# 12.net
KiCad netlist of a schematic drawn in EAGLE
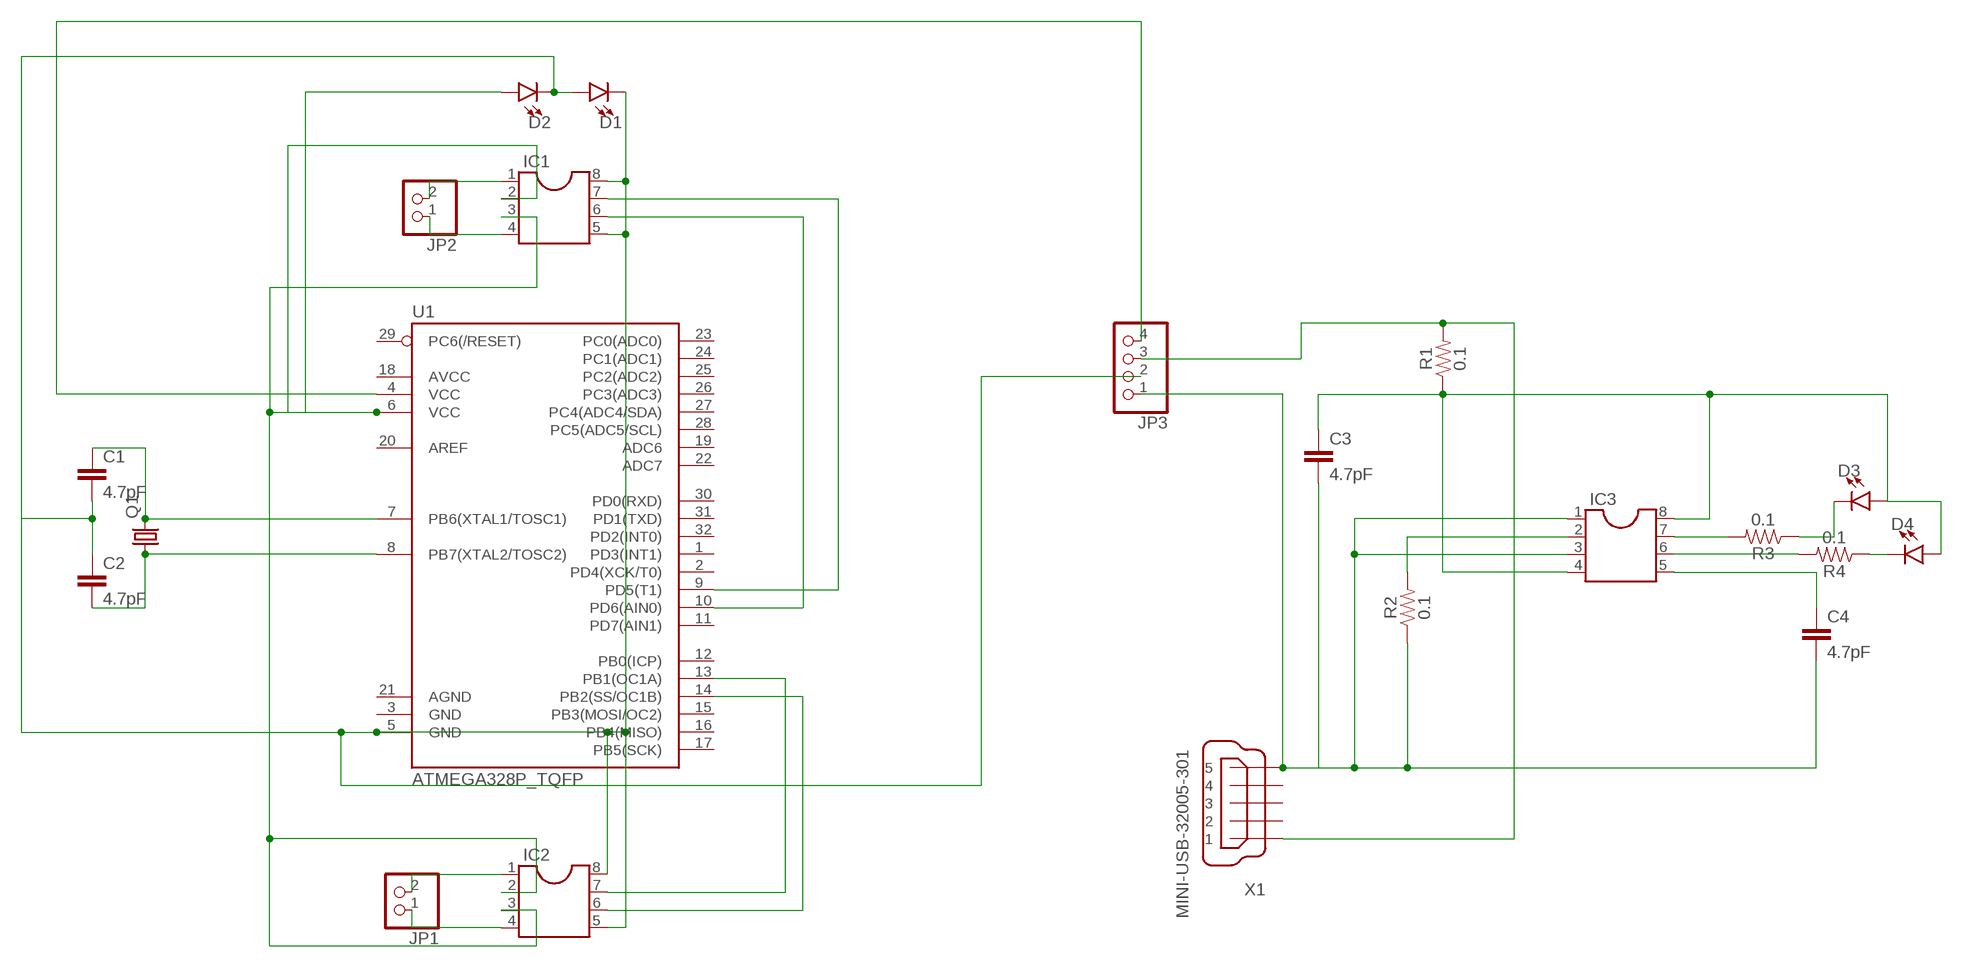
[diagram p0: schematic, sheet 1]

(export (version "E")
  (design (tool "Eeschema 10.0.6"))
  (components
    (comp (ref "C1")
      (value "4.7pF")
      (footprint "eagle-import:0603")
      (libsource (lib "eagle-import") (part "4.7PF-0603-50V-5%"))
    )
    (comp (ref "C2")
      (value "4.7pF")
      (footprint "eagle-import:0603")
      (libsource (lib "eagle-import") (part "4.7PF-0603-50V-5%"))
    )
    (comp (ref "C3")
      (value "4.7pF")
      (footprint "eagle-import:0603")
      (libsource (lib "eagle-import") (part "4.7PF-0603-50V-5%"))
    )
    (comp (ref "C4")
      (value "4.7pF")
      (footprint "eagle-import:0603")
      (libsource (lib "eagle-import") (part "4.7PF-0603-50V-5%"))
    )
    (comp (ref "D1")
      (value "LED0603")
      (footprint "eagle-import:LED-0603")
      (libsource (lib "eagle-import") (part "LED0603"))
    )
    (comp (ref "D2")
      (value "LED0603")
      (footprint "eagle-import:LED-0603")
      (libsource (lib "eagle-import") (part "LED0603"))
    )
    (comp (ref "D3")
      (value "LED0603")
      (footprint "eagle-import:LED-0603")
      (libsource (lib "eagle-import") (part "LED0603"))
    )
    (comp (ref "D4")
      (value "LED0603")
      (footprint "eagle-import:LED-0603")
      (libsource (lib "eagle-import") (part "LED0603"))
    )
    (comp (ref "IC1")
      (value "DIL8")
      (footprint "eagle-import:DIL08")
      (libsource (lib "eagle-import") (part "DIL8"))
    )
    (comp (ref "IC2")
      (value "DIL8")
      (footprint "eagle-import:DIL08")
      (libsource (lib "eagle-import") (part "DIL8"))
    )
    (comp (ref "IC3")
      (value "DIL8")
      (footprint "eagle-import:DIL08")
      (libsource (lib "eagle-import") (part "DIL8"))
    )
    (comp (ref "JP1")
      (value "PINHD-1X2")
      (footprint "eagle-import:1X02")
      (libsource (lib "eagle-import") (part "PINHD-1X2"))
    )
    (comp (ref "JP2")
      (value "PINHD-1X2")
      (footprint "eagle-import:1X02")
      (libsource (lib "eagle-import") (part "PINHD-1X2"))
    )
    (comp (ref "JP3")
      (value "PINHD-1X4")
      (footprint "eagle-import:1X04")
      (libsource (lib "eagle-import") (part "PINHD-1X4"))
    )
    (comp (ref "Q1")
      (value "CRYSTALHC49UP")
      (footprint "eagle-import:HC49UP")
      (libsource (lib "eagle-import") (part "CRYSTALHC49UP"))
    )
    (comp (ref "R1")
      (value "0.1")
      (footprint "eagle-import:1210")
      (libsource (lib "eagle-import") (part "0.1OHM-1210-1/2W-1%"))
    )
    (comp (ref "R2")
      (value "0.1")
      (footprint "eagle-import:1210")
      (libsource (lib "eagle-import") (part "0.1OHM-1210-1/2W-1%"))
    )
    (comp (ref "R3")
      (value "0.1")
      (footprint "eagle-import:1210")
      (libsource (lib "eagle-import") (part "0.1OHM-1210-1/2W-1%"))
    )
    (comp (ref "R4")
      (value "0.1")
      (footprint "eagle-import:1210")
      (libsource (lib "eagle-import") (part "0.1OHM-1210-1/2W-1%"))
    )
    (comp (ref "U1")
      (value "ATMEGA328P_TQFP")
      (footprint "eagle-import:TQFP32-08")
      (libsource (lib "eagle-import") (part "ATMEGA328P_TQFP"))
    )
    (comp (ref "X1")
      (value "MINI-USB-32005-301")
      (footprint "eagle-import:32005-301")
      (libsource (lib "eagle-import") (part "MINI-USB-32005-301"))
    )
  )
  (nets
    (net (code "1") (name "Net-(C1-Pad2)") (class "Default")
      (node (ref "C1") (pin "2") (pinfunction "2_2") (pintype "passive"))
      (node (ref "C2") (pin "1") (pinfunction "1_1") (pintype "passive"))
      (node (ref "D1") (pin "A") (pinfunction "A_A") (pintype "passive"))
      (node (ref "D1") (pin "C") (pinfunction "C_C") (pintype "passive"))
      (node (ref "D2") (pin "C") (pinfunction "C_C") (pintype "passive"))
      (node (ref "IC1") (pin "5") (pinfunction "5_5") (pintype "passive"))
      (node (ref "IC1") (pin "8") (pinfunction "8_8") (pintype "passive"))
      (node (ref "IC2") (pin "5") (pinfunction "5_5") (pintype "passive"))
      (node (ref "IC2") (pin "8") (pinfunction "8_8") (pintype "passive"))
      (node (ref "JP3") (pin "2") (pinfunction "2_2") (pintype "passive"))
      (node (ref "U1") (pin "5") (pinfunction "GND_5") (pintype "bidirectional"))
    )
    (net (code "2") (name "Net-(C3-Pad1)") (class "Default")
      (node (ref "C3") (pin "1") (pinfunction "1_1") (pintype "passive"))
      (node (ref "D3") (pin "A") (pinfunction "A_A") (pintype "passive"))
      (node (ref "D4") (pin "A") (pinfunction "A_A") (pintype "passive"))
      (node (ref "IC3") (pin "4") (pinfunction "4_4") (pintype "passive"))
      (node (ref "IC3") (pin "8") (pinfunction "8_8") (pintype "passive"))
      (node (ref "R1") (pin "1") (pinfunction "1_1") (pintype "passive"))
    )
    (net (code "3") (name "Net-(C3-Pad2)") (class "Default")
      (node (ref "C3") (pin "2") (pinfunction "2_2") (pintype "passive"))
      (node (ref "C4") (pin "2") (pinfunction "2_2") (pintype "passive"))
      (node (ref "IC3") (pin "1") (pinfunction "1_1") (pintype "passive"))
      (node (ref "IC3") (pin "3") (pinfunction "3_3") (pintype "passive"))
      (node (ref "JP3") (pin "1") (pinfunction "1_1") (pintype "passive"))
      (node (ref "R2") (pin "1") (pinfunction "1_1") (pintype "passive"))
      (node (ref "X1") (pin "5") (pinfunction "5_5") (pintype "passive"))
    )
    (net (code "4") (name "Net-(C4-Pad1)") (class "Default")
      (node (ref "C4") (pin "1") (pinfunction "1_1") (pintype "passive"))
      (node (ref "IC3") (pin "5") (pinfunction "5_5") (pintype "passive"))
    )
    (net (code "5") (name "Net-(D2-PadA)") (class "Default")
      (node (ref "D2") (pin "A") (pinfunction "A_A") (pintype "passive"))
      (node (ref "IC1") (pin "2") (pinfunction "2_2") (pintype "passive"))
      (node (ref "IC1") (pin "3") (pinfunction "3_3") (pintype "passive"))
      (node (ref "IC2") (pin "2") (pinfunction "2_2") (pintype "passive"))
      (node (ref "IC2") (pin "3") (pinfunction "3_3") (pintype "passive"))
      (node (ref "U1") (pin "6") (pinfunction "VCC_6") (pintype "bidirectional"))
    )
    (net (code "6") (name "Net-(D3-PadC)") (class "Default")
      (node (ref "D3") (pin "C") (pinfunction "C_C") (pintype "passive"))
      (node (ref "R3") (pin "1") (pinfunction "1_1") (pintype "passive"))
    )
    (net (code "7") (name "Net-(D4-PadC)") (class "Default")
      (node (ref "D4") (pin "C") (pinfunction "C_C") (pintype "passive"))
      (node (ref "R4") (pin "1") (pinfunction "1_1") (pintype "passive"))
    )
    (net (code "8") (name "Net-(IC1-Pad1)") (class "Default")
      (node (ref "IC1") (pin "1") (pinfunction "1_1") (pintype "passive"))
      (node (ref "JP2") (pin "2") (pinfunction "2_2") (pintype "passive"))
    )
    (net (code "9") (name "Net-(IC1-Pad4)") (class "Default")
      (node (ref "IC1") (pin "4") (pinfunction "4_4") (pintype "passive"))
      (node (ref "JP2") (pin "1") (pinfunction "1_1") (pintype "passive"))
    )
    (net (code "10") (name "Net-(IC2-Pad1)") (class "Default")
      (node (ref "IC2") (pin "1") (pinfunction "1_1") (pintype "passive"))
      (node (ref "JP1") (pin "2") (pinfunction "2_2") (pintype "passive"))
    )
    (net (code "11") (name "Net-(IC2-Pad4)") (class "Default")
      (node (ref "IC2") (pin "4") (pinfunction "4_4") (pintype "passive"))
      (node (ref "JP1") (pin "1") (pinfunction "1_1") (pintype "passive"))
    )
    (net (code "12") (name "Net-(IC3-Pad2)") (class "Default")
      (node (ref "IC3") (pin "2") (pinfunction "2_2") (pintype "passive"))
      (node (ref "R2") (pin "2") (pinfunction "2_2") (pintype "passive"))
    )
    (net (code "13") (name "Net-(IC3-Pad6)") (class "Default")
      (node (ref "IC3") (pin "6") (pinfunction "6_6") (pintype "passive"))
      (node (ref "R4") (pin "2") (pinfunction "2_2") (pintype "passive"))
    )
    (net (code "14") (name "Net-(IC3-Pad7)") (class "Default")
      (node (ref "IC3") (pin "7") (pinfunction "7_7") (pintype "passive"))
      (node (ref "R3") (pin "2") (pinfunction "2_2") (pintype "passive"))
    )
    (net (code "15") (name "Net-(JP3-Pad3)") (class "Default")
      (node (ref "JP3") (pin "3") (pinfunction "3_3") (pintype "passive"))
      (node (ref "R1") (pin "2") (pinfunction "2_2") (pintype "passive"))
      (node (ref "X1") (pin "1") (pinfunction "1_1") (pintype "passive"))
    )
    (net (code "16") (name "Net-(JP3-Pad4)") (class "Default")
      (node (ref "JP3") (pin "4") (pinfunction "4_4") (pintype "passive"))
      (node (ref "U1") (pin "4") (pinfunction "VCC_4") (pintype "bidirectional"))
    )
    (net (code "17") (name "Net-(U1-PB1(OC1A))") (class "Default")
      (node (ref "IC2") (pin "7") (pinfunction "7_7") (pintype "passive"))
      (node (ref "U1") (pin "13") (pinfunction "PB1(OC1A)_13") (pintype "bidirectional"))
    )
    (net (code "18") (name "Net-(U1-PB2(SS{slash}OC1B))") (class "Default")
      (node (ref "IC2") (pin "6") (pinfunction "6_6") (pintype "passive"))
      (node (ref "U1") (pin "14") (pinfunction "PB2(SS/OC1B)_14") (pintype "bidirectional"))
    )
    (net (code "19") (name "Net-(U1-PB6(XTAL1{slash}TOSC1))") (class "Default")
      (node (ref "C1") (pin "1") (pinfunction "1_1") (pintype "passive"))
      (node (ref "Q1") (pin "2") (pinfunction "2_2") (pintype "passive"))
      (node (ref "U1") (pin "7") (pinfunction "PB6(XTAL1/TOSC1)_7") (pintype "bidirectional"))
    )
    (net (code "20") (name "Net-(U1-PB7(XTAL2{slash}TOSC2))") (class "Default")
      (node (ref "C2") (pin "2") (pinfunction "2_2") (pintype "passive"))
      (node (ref "Q1") (pin "1") (pinfunction "1_1") (pintype "passive"))
      (node (ref "U1") (pin "8") (pinfunction "PB7(XTAL2/TOSC2)_8") (pintype "bidirectional"))
    )
    (net (code "21") (name "Net-(U1-PD5(T1))") (class "Default")
      (node (ref "IC1") (pin "7") (pinfunction "7_7") (pintype "passive"))
      (node (ref "U1") (pin "9") (pinfunction "PD5(T1)_9") (pintype "bidirectional"))
    )
    (net (code "22") (name "Net-(U1-PD6(AIN0))") (class "Default")
      (node (ref "IC1") (pin "6") (pinfunction "6_6") (pintype "passive"))
      (node (ref "U1") (pin "10") (pinfunction "PD6(AIN0)_10") (pintype "bidirectional"))
    )
    (net (code "23") (name "unconnected-(U1-ADC6-Pad19)") (class "Default")
      (node (ref "U1") (pin "19") (pinfunction "ADC6_19") (pintype "bidirectional"))
    )
    (net (code "24") (name "unconnected-(U1-ADC7-Pad22)") (class "Default")
      (node (ref "U1") (pin "22") (pinfunction "ADC7_22") (pintype "bidirectional"))
    )
    (net (code "25") (name "unconnected-(U1-AGND-Pad21)") (class "Default")
      (node (ref "U1") (pin "21") (pinfunction "AGND_21") (pintype "bidirectional"))
    )
    (net (code "26") (name "unconnected-(U1-AREF-Pad20)") (class "Default")
      (node (ref "U1") (pin "20") (pinfunction "AREF_20") (pintype "bidirectional"))
    )
    (net (code "27") (name "unconnected-(U1-AVCC-Pad18)") (class "Default")
      (node (ref "U1") (pin "18") (pinfunction "AVCC_18") (pintype "bidirectional"))
    )
    (net (code "28") (name "unconnected-(U1-GND-Pad3)") (class "Default")
      (node (ref "U1") (pin "3") (pinfunction "GND_3") (pintype "bidirectional"))
    )
    (net (code "29") (name "unconnected-(U1-PB0(ICP)-Pad12)") (class "Default")
      (node (ref "U1") (pin "12") (pinfunction "PB0(ICP)_12") (pintype "bidirectional"))
    )
    (net (code "30") (name "unconnected-(U1-PB3(MOSI{slash}OC2)-Pad15)") (class "Default")
      (node (ref "U1") (pin "15") (pinfunction "PB3(MOSI/OC2)_15") (pintype "bidirectional"))
    )
    (net (code "31") (name "unconnected-(U1-PB4(MISO)-Pad16)") (class "Default")
      (node (ref "U1") (pin "16") (pinfunction "PB4(MISO)_16") (pintype "bidirectional"))
    )
    (net (code "32") (name "unconnected-(U1-PB5(SCK)-Pad17)") (class "Default")
      (node (ref "U1") (pin "17") (pinfunction "PB5(SCK)_17") (pintype "bidirectional"))
    )
    (net (code "33") (name "unconnected-(U1-PC0(ADC0)-Pad23)") (class "Default")
      (node (ref "U1") (pin "23") (pinfunction "PC0(ADC0)_23") (pintype "bidirectional"))
    )
    (net (code "34") (name "unconnected-(U1-PC1(ADC1)-Pad24)") (class "Default")
      (node (ref "U1") (pin "24") (pinfunction "PC1(ADC1)_24") (pintype "bidirectional"))
    )
    (net (code "35") (name "unconnected-(U1-PC2(ADC2)-Pad25)") (class "Default")
      (node (ref "U1") (pin "25") (pinfunction "PC2(ADC2)_25") (pintype "bidirectional"))
    )
    (net (code "36") (name "unconnected-(U1-PC3(ADC3)-Pad26)") (class "Default")
      (node (ref "U1") (pin "26") (pinfunction "PC3(ADC3)_26") (pintype "bidirectional"))
    )
    (net (code "37") (name "unconnected-(U1-PC4(ADC4{slash}SDA)-Pad27)") (class "Default")
      (node (ref "U1") (pin "27") (pinfunction "PC4(ADC4/SDA)_27") (pintype "bidirectional"))
    )
    (net (code "38") (name "unconnected-(U1-PC5(ADC5{slash}SCL)-Pad28)") (class "Default")
      (node (ref "U1") (pin "28") (pinfunction "PC5(ADC5/SCL)_28") (pintype "bidirectional"))
    )
    (net (code "39") (name "unconnected-(U1-PC6({slash}RESET)-Pad29)") (class "Default")
      (node (ref "U1") (pin "29") (pinfunction "PC6(/RESET)_29") (pintype "bidirectional"))
    )
    (net (code "40") (name "unconnected-(U1-PD0(RXD)-Pad30)") (class "Default")
      (node (ref "U1") (pin "30") (pinfunction "PD0(RXD)_30") (pintype "bidirectional"))
    )
    (net (code "41") (name "unconnected-(U1-PD1(TXD)-Pad31)") (class "Default")
      (node (ref "U1") (pin "31") (pinfunction "PD1(TXD)_31") (pintype "bidirectional"))
    )
    (net (code "42") (name "unconnected-(U1-PD2(INT0)-Pad32)") (class "Default")
      (node (ref "U1") (pin "32") (pinfunction "PD2(INT0)_32") (pintype "bidirectional"))
    )
    (net (code "43") (name "unconnected-(U1-PD3(INT1)-Pad1)") (class "Default")
      (node (ref "U1") (pin "1") (pinfunction "PD3(INT1)_1") (pintype "bidirectional"))
    )
    (net (code "44") (name "unconnected-(U1-PD4(XCK{slash}T0)-Pad2)") (class "Default")
      (node (ref "U1") (pin "2") (pinfunction "PD4(XCK/T0)_2") (pintype "bidirectional"))
    )
    (net (code "45") (name "unconnected-(U1-PD7(AIN1)-Pad11)") (class "Default")
      (node (ref "U1") (pin "11") (pinfunction "PD7(AIN1)_11") (pintype "bidirectional"))
    )
    (net (code "46") (name "unconnected-(X1-Pad2)") (class "Default")
      (node (ref "X1") (pin "2") (pinfunction "2_2") (pintype "passive"))
    )
    (net (code "47") (name "unconnected-(X1-Pad3)") (class "Default")
      (node (ref "X1") (pin "3") (pinfunction "3_3") (pintype "passive"))
    )
    (net (code "48") (name "unconnected-(X1-Pad4)") (class "Default")
      (node (ref "X1") (pin "4") (pinfunction "4_4") (pintype "passive"))
    )
  )
)
